# RFID_Reader_v0_1.net
KiCad netlist of a schematic drawn in EAGLE
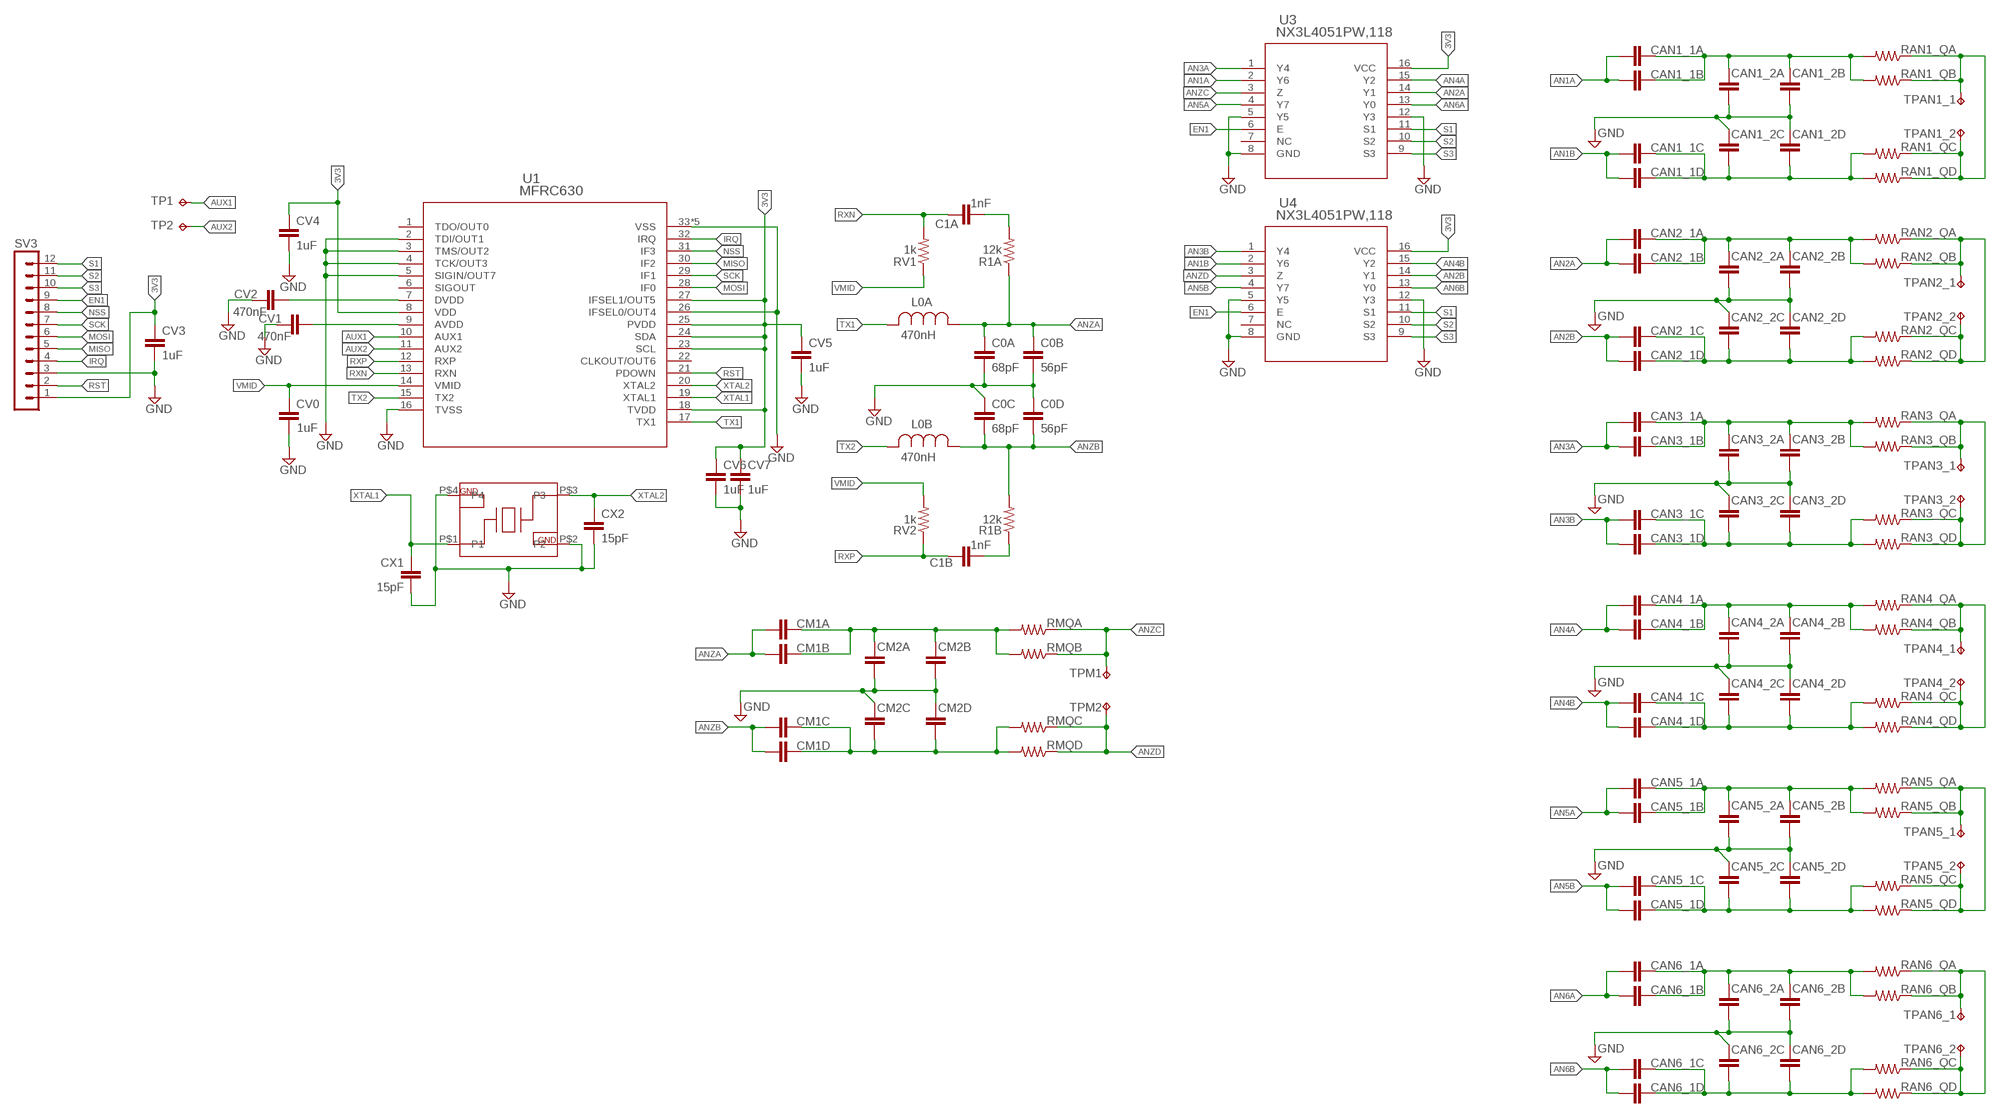
[diagram p0: schematic, sheet 1]

(export (version "E")
  (design (tool "Eeschema 10.0.6"))
  (components
    (comp (ref "C0A")
      (value "68pF")
      (footprint "eagle-import:C0805")
      (libsource (lib "eagle-import") (part "C-EUC0805"))
    )
    (comp (ref "C0B")
      (value "56pF")
      (footprint "eagle-import:C0805")
      (libsource (lib "eagle-import") (part "C-EUC0805"))
    )
    (comp (ref "C0C")
      (value "68pF")
      (footprint "eagle-import:C0805")
      (libsource (lib "eagle-import") (part "C-EUC0805"))
    )
    (comp (ref "C0D")
      (value "56pF")
      (footprint "eagle-import:C0805")
      (libsource (lib "eagle-import") (part "C-EUC0805"))
    )
    (comp (ref "C1A")
      (value "1nF")
      (footprint "eagle-import:C0805")
      (libsource (lib "eagle-import") (part "C-EUC0805"))
    )
    (comp (ref "C1B")
      (value "1nF")
      (footprint "eagle-import:C0805")
      (libsource (lib "eagle-import") (part "C-EUC0805"))
    )
    (comp (ref "CAN1_1A")
      (value "C-EUC0805")
      (footprint "eagle-import:C0805")
      (libsource (lib "eagle-import") (part "C-EUC0805"))
    )
    (comp (ref "CAN1_1B")
      (value "C-EUC0805")
      (footprint "eagle-import:C0805")
      (libsource (lib "eagle-import") (part "C-EUC0805"))
    )
    (comp (ref "CAN1_1C")
      (value "C-EUC0805")
      (footprint "eagle-import:C0805")
      (libsource (lib "eagle-import") (part "C-EUC0805"))
    )
    (comp (ref "CAN1_1D")
      (value "C-EUC0805")
      (footprint "eagle-import:C0805")
      (libsource (lib "eagle-import") (part "C-EUC0805"))
    )
    (comp (ref "CAN1_2A")
      (value "C-EUC0805")
      (footprint "eagle-import:C0805")
      (libsource (lib "eagle-import") (part "C-EUC0805"))
    )
    (comp (ref "CAN1_2B")
      (value "C-EUC0805")
      (footprint "eagle-import:C0805")
      (libsource (lib "eagle-import") (part "C-EUC0805"))
    )
    (comp (ref "CAN1_2C")
      (value "C-EUC0805")
      (footprint "eagle-import:C0805")
      (libsource (lib "eagle-import") (part "C-EUC0805"))
    )
    (comp (ref "CAN1_2D")
      (value "C-EUC0805")
      (footprint "eagle-import:C0805")
      (libsource (lib "eagle-import") (part "C-EUC0805"))
    )
    (comp (ref "CAN2_1A")
      (value "C-EUC0805")
      (footprint "eagle-import:C0805")
      (libsource (lib "eagle-import") (part "C-EUC0805"))
    )
    (comp (ref "CAN2_1B")
      (value "C-EUC0805")
      (footprint "eagle-import:C0805")
      (libsource (lib "eagle-import") (part "C-EUC0805"))
    )
    (comp (ref "CAN2_1C")
      (value "C-EUC0805")
      (footprint "eagle-import:C0805")
      (libsource (lib "eagle-import") (part "C-EUC0805"))
    )
    (comp (ref "CAN2_1D")
      (value "C-EUC0805")
      (footprint "eagle-import:C0805")
      (libsource (lib "eagle-import") (part "C-EUC0805"))
    )
    (comp (ref "CAN2_2A")
      (value "C-EUC0805")
      (footprint "eagle-import:C0805")
      (libsource (lib "eagle-import") (part "C-EUC0805"))
    )
    (comp (ref "CAN2_2B")
      (value "C-EUC0805")
      (footprint "eagle-import:C0805")
      (libsource (lib "eagle-import") (part "C-EUC0805"))
    )
    (comp (ref "CAN2_2C")
      (value "C-EUC0805")
      (footprint "eagle-import:C0805")
      (libsource (lib "eagle-import") (part "C-EUC0805"))
    )
    (comp (ref "CAN2_2D")
      (value "C-EUC0805")
      (footprint "eagle-import:C0805")
      (libsource (lib "eagle-import") (part "C-EUC0805"))
    )
    (comp (ref "CAN3_1A")
      (value "C-EUC0805")
      (footprint "eagle-import:C0805")
      (libsource (lib "eagle-import") (part "C-EUC0805"))
    )
    (comp (ref "CAN3_1B")
      (value "C-EUC0805")
      (footprint "eagle-import:C0805")
      (libsource (lib "eagle-import") (part "C-EUC0805"))
    )
    (comp (ref "CAN3_1C")
      (value "C-EUC0805")
      (footprint "eagle-import:C0805")
      (libsource (lib "eagle-import") (part "C-EUC0805"))
    )
    (comp (ref "CAN3_1D")
      (value "C-EUC0805")
      (footprint "eagle-import:C0805")
      (libsource (lib "eagle-import") (part "C-EUC0805"))
    )
    (comp (ref "CAN3_2A")
      (value "C-EUC0805")
      (footprint "eagle-import:C0805")
      (libsource (lib "eagle-import") (part "C-EUC0805"))
    )
    (comp (ref "CAN3_2B")
      (value "C-EUC0805")
      (footprint "eagle-import:C0805")
      (libsource (lib "eagle-import") (part "C-EUC0805"))
    )
    (comp (ref "CAN3_2C")
      (value "C-EUC0805")
      (footprint "eagle-import:C0805")
      (libsource (lib "eagle-import") (part "C-EUC0805"))
    )
    (comp (ref "CAN3_2D")
      (value "C-EUC0805")
      (footprint "eagle-import:C0805")
      (libsource (lib "eagle-import") (part "C-EUC0805"))
    )
    (comp (ref "CAN4_1A")
      (value "C-EUC0805")
      (footprint "eagle-import:C0805")
      (libsource (lib "eagle-import") (part "C-EUC0805"))
    )
    (comp (ref "CAN4_1B")
      (value "C-EUC0805")
      (footprint "eagle-import:C0805")
      (libsource (lib "eagle-import") (part "C-EUC0805"))
    )
    (comp (ref "CAN4_1C")
      (value "C-EUC0805")
      (footprint "eagle-import:C0805")
      (libsource (lib "eagle-import") (part "C-EUC0805"))
    )
    (comp (ref "CAN4_1D")
      (value "C-EUC0805")
      (footprint "eagle-import:C0805")
      (libsource (lib "eagle-import") (part "C-EUC0805"))
    )
    (comp (ref "CAN4_2A")
      (value "C-EUC0805")
      (footprint "eagle-import:C0805")
      (libsource (lib "eagle-import") (part "C-EUC0805"))
    )
    (comp (ref "CAN4_2B")
      (value "C-EUC0805")
      (footprint "eagle-import:C0805")
      (libsource (lib "eagle-import") (part "C-EUC0805"))
    )
    (comp (ref "CAN4_2C")
      (value "C-EUC0805")
      (footprint "eagle-import:C0805")
      (libsource (lib "eagle-import") (part "C-EUC0805"))
    )
    (comp (ref "CAN4_2D")
      (value "C-EUC0805")
      (footprint "eagle-import:C0805")
      (libsource (lib "eagle-import") (part "C-EUC0805"))
    )
    (comp (ref "CAN5_1A")
      (value "C-EUC0805")
      (footprint "eagle-import:C0805")
      (libsource (lib "eagle-import") (part "C-EUC0805"))
    )
    (comp (ref "CAN5_1B")
      (value "C-EUC0805")
      (footprint "eagle-import:C0805")
      (libsource (lib "eagle-import") (part "C-EUC0805"))
    )
    (comp (ref "CAN5_1C")
      (value "C-EUC0805")
      (footprint "eagle-import:C0805")
      (libsource (lib "eagle-import") (part "C-EUC0805"))
    )
    (comp (ref "CAN5_1D")
      (value "C-EUC0805")
      (footprint "eagle-import:C0805")
      (libsource (lib "eagle-import") (part "C-EUC0805"))
    )
    (comp (ref "CAN5_2A")
      (value "C-EUC0805")
      (footprint "eagle-import:C0805")
      (libsource (lib "eagle-import") (part "C-EUC0805"))
    )
    (comp (ref "CAN5_2B")
      (value "C-EUC0805")
      (footprint "eagle-import:C0805")
      (libsource (lib "eagle-import") (part "C-EUC0805"))
    )
    (comp (ref "CAN5_2C")
      (value "C-EUC0805")
      (footprint "eagle-import:C0805")
      (libsource (lib "eagle-import") (part "C-EUC0805"))
    )
    (comp (ref "CAN5_2D")
      (value "C-EUC0805")
      (footprint "eagle-import:C0805")
      (libsource (lib "eagle-import") (part "C-EUC0805"))
    )
    (comp (ref "CAN6_1A")
      (value "C-EUC0805")
      (footprint "eagle-import:C0805")
      (libsource (lib "eagle-import") (part "C-EUC0805"))
    )
    (comp (ref "CAN6_1B")
      (value "C-EUC0805")
      (footprint "eagle-import:C0805")
      (libsource (lib "eagle-import") (part "C-EUC0805"))
    )
    (comp (ref "CAN6_1C")
      (value "C-EUC0805")
      (footprint "eagle-import:C0805")
      (libsource (lib "eagle-import") (part "C-EUC0805"))
    )
    (comp (ref "CAN6_1D")
      (value "C-EUC0805")
      (footprint "eagle-import:C0805")
      (libsource (lib "eagle-import") (part "C-EUC0805"))
    )
    (comp (ref "CAN6_2A")
      (value "C-EUC0805")
      (footprint "eagle-import:C0805")
      (libsource (lib "eagle-import") (part "C-EUC0805"))
    )
    (comp (ref "CAN6_2B")
      (value "C-EUC0805")
      (footprint "eagle-import:C0805")
      (libsource (lib "eagle-import") (part "C-EUC0805"))
    )
    (comp (ref "CAN6_2C")
      (value "C-EUC0805")
      (footprint "eagle-import:C0805")
      (libsource (lib "eagle-import") (part "C-EUC0805"))
    )
    (comp (ref "CAN6_2D")
      (value "C-EUC0805")
      (footprint "eagle-import:C0805")
      (libsource (lib "eagle-import") (part "C-EUC0805"))
    )
    (comp (ref "CM1A")
      (value "C-EUC0805")
      (footprint "eagle-import:C0805")
      (libsource (lib "eagle-import") (part "C-EUC0805"))
    )
    (comp (ref "CM1B")
      (value "C-EUC0805")
      (footprint "eagle-import:C0805")
      (libsource (lib "eagle-import") (part "C-EUC0805"))
    )
    (comp (ref "CM1C")
      (value "C-EUC0805")
      (footprint "eagle-import:C0805")
      (libsource (lib "eagle-import") (part "C-EUC0805"))
    )
    (comp (ref "CM1D")
      (value "C-EUC0805")
      (footprint "eagle-import:C0805")
      (libsource (lib "eagle-import") (part "C-EUC0805"))
    )
    (comp (ref "CM2A")
      (value "C-EUC0805")
      (footprint "eagle-import:C0805")
      (libsource (lib "eagle-import") (part "C-EUC0805"))
    )
    (comp (ref "CM2B")
      (value "C-EUC0805")
      (footprint "eagle-import:C0805")
      (libsource (lib "eagle-import") (part "C-EUC0805"))
    )
    (comp (ref "CM2C")
      (value "C-EUC0805")
      (footprint "eagle-import:C0805")
      (libsource (lib "eagle-import") (part "C-EUC0805"))
    )
    (comp (ref "CM2D")
      (value "C-EUC0805")
      (footprint "eagle-import:C0805")
      (libsource (lib "eagle-import") (part "C-EUC0805"))
    )
    (comp (ref "CV0")
      (value "1uF")
      (footprint "eagle-import:C0402")
      (libsource (lib "eagle-import") (part "C-EUC0402"))
    )
    (comp (ref "CV1")
      (value "470nF")
      (footprint "eagle-import:C0402")
      (libsource (lib "eagle-import") (part "C-EUC0402"))
    )
    (comp (ref "CV2")
      (value "470nF")
      (footprint "eagle-import:C0402")
      (libsource (lib "eagle-import") (part "C-EUC0402"))
    )
    (comp (ref "CV3")
      (value "1uF")
      (footprint "eagle-import:C0402")
      (libsource (lib "eagle-import") (part "C-EUC0402"))
    )
    (comp (ref "CV4")
      (value "1uF")
      (footprint "eagle-import:C0402")
      (libsource (lib "eagle-import") (part "C-EUC0402"))
    )
    (comp (ref "CV5")
      (value "1uF")
      (footprint "eagle-import:C0402")
      (libsource (lib "eagle-import") (part "C-EUC0402"))
    )
    (comp (ref "CV6")
      (value "1uF")
      (footprint "eagle-import:C0402")
      (libsource (lib "eagle-import") (part "C-EUC0402"))
    )
    (comp (ref "CV7")
      (value "1uF")
      (footprint "eagle-import:C0402")
      (libsource (lib "eagle-import") (part "C-EUC0402"))
    )
    (comp (ref "CX1")
      (value "15pF")
      (footprint "eagle-import:C0402")
      (libsource (lib "eagle-import") (part "C-EUC0402"))
    )
    (comp (ref "CX2")
      (value "15pF")
      (footprint "eagle-import:C0402")
      (libsource (lib "eagle-import") (part "C-EUC0402"))
    )
    (comp (ref "L0A")
      (value "470nH")
      (footprint "eagle-import:IND_BOURNS_CE201210_C")
      (fields
        (field (name "MANUFACTURER_PART_NUMBER") "CE201210-R47J")
        (field (name "COPYRIGHT") "Copyright (C) 2024 Ultra Librarian. All rights reserved.")
      )
      (libsource (lib "eagle-import") (part "CE201210-R47JIND_BOURNS_CE201210_C"))
    )
    (comp (ref "L0B")
      (value "470nH")
      (footprint "eagle-import:IND_BOURNS_CE201210_C")
      (fields
        (field (name "MANUFACTURER_PART_NUMBER") "CE201210-R47J")
        (field (name "COPYRIGHT") "Copyright (C) 2024 Ultra Librarian. All rights reserved.")
      )
      (libsource (lib "eagle-import") (part "CE201210-R47JIND_BOURNS_CE201210_C"))
    )
    (comp (ref "R1A")
      (value "12k")
      (footprint "eagle-import:R0805")
      (libsource (lib "eagle-import") (part "R-US_R0805"))
    )
    (comp (ref "R1B")
      (value "12k")
      (footprint "eagle-import:R0805")
      (libsource (lib "eagle-import") (part "R-US_R0805"))
    )
    (comp (ref "RAN1_QA")
      (value "R-US_R0805")
      (footprint "eagle-import:R0805")
      (libsource (lib "eagle-import") (part "R-US_R0805"))
    )
    (comp (ref "RAN1_QB")
      (value "R-US_R0805")
      (footprint "eagle-import:R0805")
      (libsource (lib "eagle-import") (part "R-US_R0805"))
    )
    (comp (ref "RAN1_QC")
      (value "R-US_R0805")
      (footprint "eagle-import:R0805")
      (libsource (lib "eagle-import") (part "R-US_R0805"))
    )
    (comp (ref "RAN1_QD")
      (value "R-US_R0805")
      (footprint "eagle-import:R0805")
      (libsource (lib "eagle-import") (part "R-US_R0805"))
    )
    (comp (ref "RAN2_QA")
      (value "R-US_R0805")
      (footprint "eagle-import:R0805")
      (libsource (lib "eagle-import") (part "R-US_R0805"))
    )
    (comp (ref "RAN2_QB")
      (value "R-US_R0805")
      (footprint "eagle-import:R0805")
      (libsource (lib "eagle-import") (part "R-US_R0805"))
    )
    (comp (ref "RAN2_QC")
      (value "R-US_R0805")
      (footprint "eagle-import:R0805")
      (libsource (lib "eagle-import") (part "R-US_R0805"))
    )
    (comp (ref "RAN2_QD")
      (value "R-US_R0805")
      (footprint "eagle-import:R0805")
      (libsource (lib "eagle-import") (part "R-US_R0805"))
    )
    (comp (ref "RAN3_QA")
      (value "R-US_R0805")
      (footprint "eagle-import:R0805")
      (libsource (lib "eagle-import") (part "R-US_R0805"))
    )
    (comp (ref "RAN3_QB")
      (value "R-US_R0805")
      (footprint "eagle-import:R0805")
      (libsource (lib "eagle-import") (part "R-US_R0805"))
    )
    (comp (ref "RAN3_QC")
      (value "R-US_R0805")
      (footprint "eagle-import:R0805")
      (libsource (lib "eagle-import") (part "R-US_R0805"))
    )
    (comp (ref "RAN3_QD")
      (value "R-US_R0805")
      (footprint "eagle-import:R0805")
      (libsource (lib "eagle-import") (part "R-US_R0805"))
    )
    (comp (ref "RAN4_QA")
      (value "R-US_R0805")
      (footprint "eagle-import:R0805")
      (libsource (lib "eagle-import") (part "R-US_R0805"))
    )
    (comp (ref "RAN4_QB")
      (value "R-US_R0805")
      (footprint "eagle-import:R0805")
      (libsource (lib "eagle-import") (part "R-US_R0805"))
    )
    (comp (ref "RAN4_QC")
      (value "R-US_R0805")
      (footprint "eagle-import:R0805")
      (libsource (lib "eagle-import") (part "R-US_R0805"))
    )
    (comp (ref "RAN4_QD")
      (value "R-US_R0805")
      (footprint "eagle-import:R0805")
      (libsource (lib "eagle-import") (part "R-US_R0805"))
    )
    (comp (ref "RAN5_QA")
      (value "R-US_R0805")
      (footprint "eagle-import:R0805")
      (libsource (lib "eagle-import") (part "R-US_R0805"))
    )
    (comp (ref "RAN5_QB")
      (value "R-US_R0805")
      (footprint "eagle-import:R0805")
      (libsource (lib "eagle-import") (part "R-US_R0805"))
    )
    (comp (ref "RAN5_QC")
      (value "R-US_R0805")
      (footprint "eagle-import:R0805")
      (libsource (lib "eagle-import") (part "R-US_R0805"))
    )
    (comp (ref "RAN5_QD")
      (value "R-US_R0805")
      (footprint "eagle-import:R0805")
      (libsource (lib "eagle-import") (part "R-US_R0805"))
    )
    (comp (ref "RAN6_QA")
      (value "R-US_R0805")
      (footprint "eagle-import:R0805")
      (libsource (lib "eagle-import") (part "R-US_R0805"))
    )
    (comp (ref "RAN6_QB")
      (value "R-US_R0805")
      (footprint "eagle-import:R0805")
      (libsource (lib "eagle-import") (part "R-US_R0805"))
    )
    (comp (ref "RAN6_QC")
      (value "R-US_R0805")
      (footprint "eagle-import:R0805")
      (libsource (lib "eagle-import") (part "R-US_R0805"))
    )
    (comp (ref "RAN6_QD")
      (value "R-US_R0805")
      (footprint "eagle-import:R0805")
      (libsource (lib "eagle-import") (part "R-US_R0805"))
    )
    (comp (ref "RMQA")
      (value "R-US_R0805")
      (footprint "eagle-import:R0805")
      (libsource (lib "eagle-import") (part "R-US_R0805"))
    )
    (comp (ref "RMQB")
      (value "R-US_R0805")
      (footprint "eagle-import:R0805")
      (libsource (lib "eagle-import") (part "R-US_R0805"))
    )
    (comp (ref "RMQC")
      (value "R-US_R0805")
      (footprint "eagle-import:R0805")
      (libsource (lib "eagle-import") (part "R-US_R0805"))
    )
    (comp (ref "RMQD")
      (value "R-US_R0805")
      (footprint "eagle-import:R0805")
      (libsource (lib "eagle-import") (part "R-US_R0805"))
    )
    (comp (ref "RV1")
      (value "1k")
      (footprint "eagle-import:R0805")
      (libsource (lib "eagle-import") (part "R-US_R0805"))
    )
    (comp (ref "RV2")
      (value "1k")
      (footprint "eagle-import:R0805")
      (libsource (lib "eagle-import") (part "R-US_R0805"))
    )
    (comp (ref "SV3")
      (value "MA12-1")
      (footprint "eagle-import:MA12-1")
      (libsource (lib "eagle-import") (part "MA12-1"))
    )
    (comp (ref "TP1")
      (value "TPTP10R")
      (footprint "eagle-import:TP10R")
      (libsource (lib "eagle-import") (part "TPTP10R"))
    )
    (comp (ref "TP2")
      (value "TPTP10R")
      (footprint "eagle-import:TP10R")
      (libsource (lib "eagle-import") (part "TPTP10R"))
    )
    (comp (ref "TPAN1_1")
      (value "TPTP10R")
      (footprint "eagle-import:TP10R")
      (libsource (lib "eagle-import") (part "TPTP10R"))
    )
    (comp (ref "TPAN1_2")
      (value "TPTP10R")
      (footprint "eagle-import:TP10R")
      (libsource (lib "eagle-import") (part "TPTP10R"))
    )
    (comp (ref "TPAN2_1")
      (value "TPTP10R")
      (footprint "eagle-import:TP10R")
      (libsource (lib "eagle-import") (part "TPTP10R"))
    )
    (comp (ref "TPAN2_2")
      (value "TPTP10R")
      (footprint "eagle-import:TP10R")
      (libsource (lib "eagle-import") (part "TPTP10R"))
    )
    (comp (ref "TPAN3_1")
      (value "TPTP10R")
      (footprint "eagle-import:TP10R")
      (libsource (lib "eagle-import") (part "TPTP10R"))
    )
    (comp (ref "TPAN3_2")
      (value "TPTP10R")
      (footprint "eagle-import:TP10R")
      (libsource (lib "eagle-import") (part "TPTP10R"))
    )
    (comp (ref "TPAN4_1")
      (value "TPTP10R")
      (footprint "eagle-import:TP10R")
      (libsource (lib "eagle-import") (part "TPTP10R"))
    )
    (comp (ref "TPAN4_2")
      (value "TPTP10R")
      (footprint "eagle-import:TP10R")
      (libsource (lib "eagle-import") (part "TPTP10R"))
    )
    (comp (ref "TPAN5_1")
      (value "TPTP10R")
      (footprint "eagle-import:TP10R")
      (libsource (lib "eagle-import") (part "TPTP10R"))
    )
    (comp (ref "TPAN5_2")
      (value "TPTP10R")
      (footprint "eagle-import:TP10R")
      (libsource (lib "eagle-import") (part "TPTP10R"))
    )
    (comp (ref "TPAN6_1")
      (value "TPTP10R")
      (footprint "eagle-import:TP10R")
      (libsource (lib "eagle-import") (part "TPTP10R"))
    )
    (comp (ref "TPAN6_2")
      (value "TPTP10R")
      (footprint "eagle-import:TP10R")
      (libsource (lib "eagle-import") (part "TPTP10R"))
    )
    (comp (ref "TPM1")
      (value "TPTP10R")
      (footprint "eagle-import:TP10R")
      (libsource (lib "eagle-import") (part "TPTP10R"))
    )
    (comp (ref "TPM2")
      (value "TPTP10R")
      (footprint "eagle-import:TP10R")
      (libsource (lib "eagle-import") (part "TPTP10R"))
    )
    (comp (ref "U1")
      (value "MFRC630")
      (footprint "eagle-import:HVQFN32_SOT617-1_NXP-M")
      (fields
        (field (name "MANUFACTURER_PART_NUMBER") "MFRC63002HN,118")
        (field (name "COPYRIGHT") "Copyright (C) 2024 Ultra Librarian. All rights reserved.")
      )
      (libsource (lib "eagle-import") (part "MFRC63002HN,118HVQFN32_SOT617-1_NXP-M"))
    )
    (comp (ref "U2")
      (value "E3SB27")
      (footprint "eagle-import:DFN320X250X75-4N")
      (libsource (lib "eagle-import") (part "E3SB27E0X000VEE3SB27E0X000VE"))
    )
    (comp (ref "U3")
      (value "NX3L4051PW,118")
      (footprint "eagle-import:TSSOP16_NXP-M")
      (fields (field (name "COPYRIGHT") "Copyright (C) 2024 Ultra Librarian. All rights reserved."))
      (libsource (lib "eagle-import") (part "NX3L4051PW,118TSSOP16_NXP-M"))
    )
    (comp (ref "U4")
      (value "NX3L4051PW,118")
      (footprint "eagle-import:TSSOP16_NXP-M")
      (fields (field (name "COPYRIGHT") "Copyright (C) 2024 Ultra Librarian. All rights reserved."))
      (libsource (lib "eagle-import") (part "NX3L4051PW,118TSSOP16_NXP-M"))
    )
  )
  (nets
    (net (code "1") (name "3V3") (class "Default")
      (node (ref "CV3") (pin "1") (pinfunction "1_1") (pintype "passive"))
      (node (ref "CV4") (pin "1") (pinfunction "1_1") (pintype "passive"))
      (node (ref "CV5") (pin "1") (pinfunction "1_1") (pintype "passive"))
      (node (ref "CV6") (pin "1") (pinfunction "1_1") (pintype "passive"))
      (node (ref "CV7") (pin "1") (pinfunction "1_1") (pintype "passive"))
      (node (ref "SV3") (pin "1") (pinfunction "1_1") (pintype "passive"))
      (node (ref "U1") (pin "18") (pinfunction "TVDD_18") (pintype "power_in"))
      (node (ref "U1") (pin "23") (pinfunction "SCL_23") (pintype "output"))
      (node (ref "U1") (pin "24") (pinfunction "SDA_24") (pintype "bidirectional"))
      (node (ref "U1") (pin "25") (pinfunction "PVDD_25") (pintype "power_in"))
      (node (ref "U1") (pin "27") (pinfunction "IFSEL1/OUT5_27") (pintype "input"))
      (node (ref "U1") (pin "8") (pinfunction "VDD_8") (pintype "power_in"))
      (node (ref "U3") (pin "16") (pinfunction "VCC_16") (pintype "power_in"))
      (node (ref "U4") (pin "16") (pinfunction "VCC_16") (pintype "power_in"))
    )
    (net (code "2") (name "AN1A") (class "Default")
      (node (ref "CAN1_1A") (pin "2") (pinfunction "2_2") (pintype "passive"))
      (node (ref "CAN1_1B") (pin "2") (pinfunction "2_2") (pintype "passive"))
      (node (ref "U3") (pin "2") (pinfunction "Y6_2") (pintype "bidirectional"))
    )
    (net (code "3") (name "AN1B") (class "Default")
      (node (ref "CAN1_1C") (pin "2") (pinfunction "2_2") (pintype "passive"))
      (node (ref "CAN1_1D") (pin "2") (pinfunction "2_2") (pintype "passive"))
      (node (ref "U4") (pin "2") (pinfunction "Y6_2") (pintype "bidirectional"))
    )
    (net (code "4") (name "AN2A") (class "Default")
      (node (ref "CAN2_1A") (pin "2") (pinfunction "2_2") (pintype "passive"))
      (node (ref "CAN2_1B") (pin "2") (pinfunction "2_2") (pintype "passive"))
      (node (ref "U3") (pin "14") (pinfunction "Y1_14") (pintype "bidirectional"))
    )
    (net (code "5") (name "AN2B") (class "Default")
      (node (ref "CAN2_1C") (pin "2") (pinfunction "2_2") (pintype "passive"))
      (node (ref "CAN2_1D") (pin "2") (pinfunction "2_2") (pintype "passive"))
      (node (ref "U4") (pin "14") (pinfunction "Y1_14") (pintype "bidirectional"))
    )
    (net (code "6") (name "AN3A") (class "Default")
      (node (ref "CAN3_1A") (pin "2") (pinfunction "2_2") (pintype "passive"))
      (node (ref "CAN3_1B") (pin "2") (pinfunction "2_2") (pintype "passive"))
      (node (ref "U3") (pin "1") (pinfunction "Y4_1") (pintype "bidirectional"))
    )
    (net (code "7") (name "AN3B") (class "Default")
      (node (ref "CAN3_1C") (pin "2") (pinfunction "2_2") (pintype "passive"))
      (node (ref "CAN3_1D") (pin "2") (pinfunction "2_2") (pintype "passive"))
      (node (ref "U4") (pin "1") (pinfunction "Y4_1") (pintype "bidirectional"))
    )
    (net (code "8") (name "AN4A") (class "Default")
      (node (ref "CAN4_1A") (pin "2") (pinfunction "2_2") (pintype "passive"))
      (node (ref "CAN4_1B") (pin "2") (pinfunction "2_2") (pintype "passive"))
      (node (ref "U3") (pin "15") (pinfunction "Y2_15") (pintype "bidirectional"))
    )
    (net (code "9") (name "AN4B") (class "Default")
      (node (ref "CAN4_1C") (pin "2") (pinfunction "2_2") (pintype "passive"))
      (node (ref "CAN4_1D") (pin "2") (pinfunction "2_2") (pintype "passive"))
      (node (ref "U4") (pin "15") (pinfunction "Y2_15") (pintype "bidirectional"))
    )
    (net (code "10") (name "AN5A") (class "Default")
      (node (ref "CAN5_1A") (pin "2") (pinfunction "2_2") (pintype "passive"))
      (node (ref "CAN5_1B") (pin "2") (pinfunction "2_2") (pintype "passive"))
      (node (ref "U3") (pin "4") (pinfunction "Y7_4") (pintype "bidirectional"))
    )
    (net (code "11") (name "AN5B") (class "Default")
      (node (ref "CAN5_1C") (pin "2") (pinfunction "2_2") (pintype "passive"))
      (node (ref "CAN5_1D") (pin "2") (pinfunction "2_2") (pintype "passive"))
      (node (ref "U4") (pin "4") (pinfunction "Y7_4") (pintype "bidirectional"))
    )
    (net (code "12") (name "AN6A") (class "Default")
      (node (ref "CAN6_1A") (pin "2") (pinfunction "2_2") (pintype "passive"))
      (node (ref "CAN6_1B") (pin "2") (pinfunction "2_2") (pintype "passive"))
      (node (ref "U3") (pin "13") (pinfunction "Y0_13") (pintype "bidirectional"))
    )
    (net (code "13") (name "AN6B") (class "Default")
      (node (ref "CAN6_1C") (pin "2") (pinfunction "2_2") (pintype "passive"))
      (node (ref "CAN6_1D") (pin "2") (pinfunction "2_2") (pintype "passive"))
      (node (ref "U4") (pin "13") (pinfunction "Y0_13") (pintype "bidirectional"))
    )
    (net (code "14") (name "ANZA") (class "Default")
      (node (ref "C0A") (pin "1") (pinfunction "1_1") (pintype "passive"))
      (node (ref "C0B") (pin "1") (pinfunction "1_1") (pintype "passive"))
      (node (ref "CM1A") (pin "2") (pinfunction "2_2") (pintype "passive"))
      (node (ref "CM1B") (pin "2") (pinfunction "2_2") (pintype "passive"))
      (node (ref "L0A") (pin "1") (pinfunction "1_1") (pintype "passive"))
      (node (ref "R1A") (pin "1") (pinfunction "1_1") (pintype "passive"))
    )
    (net (code "15") (name "ANZB") (class "Default")
      (node (ref "C0C") (pin "2") (pinfunction "2_2") (pintype "passive"))
      (node (ref "C0D") (pin "2") (pinfunction "2_2") (pintype "passive"))
      (node (ref "CM1C") (pin "2") (pinfunction "2_2") (pintype "passive"))
      (node (ref "CM1D") (pin "2") (pinfunction "2_2") (pintype "passive"))
      (node (ref "L0B") (pin "1") (pinfunction "1_1") (pintype "passive"))
      (node (ref "R1B") (pin "2") (pinfunction "2_2") (pintype "passive"))
    )
    (net (code "16") (name "ANZC") (class "Default")
      (node (ref "RMQA") (pin "1") (pinfunction "1_1") (pintype "passive"))
      (node (ref "RMQB") (pin "1") (pinfunction "1_1") (pintype "passive"))
      (node (ref "TPM1") (pin "TP") (pinfunction "TP_TP") (pintype "input"))
      (node (ref "U3") (pin "3") (pinfunction "Z_3") (pintype "bidirectional"))
    )
    (net (code "17") (name "ANZD") (class "Default")
      (node (ref "RMQC") (pin "1") (pinfunction "1_1") (pintype "passive"))
      (node (ref "RMQD") (pin "1") (pinfunction "1_1") (pintype "passive"))
      (node (ref "TPM2") (pin "TP") (pinfunction "TP_TP") (pintype "input"))
      (node (ref "U4") (pin "3") (pinfunction "Z_3") (pintype "bidirectional"))
    )
    (net (code "18") (name "AUX1") (class "Default")
      (node (ref "TP1") (pin "TP") (pinfunction "TP_TP") (pintype "input"))
      (node (ref "U1") (pin "10") (pinfunction "AUX1_10") (pintype "output"))
    )
    (net (code "19") (name "AUX2") (class "Default")
      (node (ref "TP2") (pin "TP") (pinfunction "TP_TP") (pintype "input"))
      (node (ref "U1") (pin "11") (pinfunction "AUX2_11") (pintype "output"))
    )
    (net (code "20") (name "EN1") (class "Default")
      (node (ref "SV3") (pin "9") (pinfunction "9_9") (pintype "passive"))
      (node (ref "U3") (pin "6") (pinfunction "E_6") (pintype "input"))
      (node (ref "U4") (pin "6") (pinfunction "E_6") (pintype "input"))
    )
    (net (code "21") (name "GND") (class "Default")
      (node (ref "C0A") (pin "2") (pinfunction "2_2") (pintype "passive"))
      (node (ref "C0B") (pin "2") (pinfunction "2_2") (pintype "passive"))
      (node (ref "C0C") (pin "1") (pinfunction "1_1") (pintype "passive"))
      (node (ref "C0D") (pin "1") (pinfunction "1_1") (pintype "passive"))
      (node (ref "CAN1_2A") (pin "2") (pinfunction "2_2") (pintype "passive"))
      (node (ref "CAN1_2B") (pin "2") (pinfunction "2_2") (pintype "passive"))
      (node (ref "CAN1_2C") (pin "1") (pinfunction "1_1") (pintype "passive"))
      (node (ref "CAN1_2D") (pin "1") (pinfunction "1_1") (pintype "passive"))
      (node (ref "CAN2_2A") (pin "2") (pinfunction "2_2") (pintype "passive"))
      (node (ref "CAN2_2B") (pin "2") (pinfunction "2_2") (pintype "passive"))
      (node (ref "CAN2_2C") (pin "1") (pinfunction "1_1") (pintype "passive"))
      (node (ref "CAN2_2D") (pin "1") (pinfunction "1_1") (pintype "passive"))
      (node (ref "CAN3_2A") (pin "2") (pinfunction "2_2") (pintype "passive"))
      (node (ref "CAN3_2B") (pin "2") (pinfunction "2_2") (pintype "passive"))
      (node (ref "CAN3_2C") (pin "1") (pinfunction "1_1") (pintype "passive"))
      (node (ref "CAN3_2D") (pin "1") (pinfunction "1_1") (pintype "passive"))
      (node (ref "CAN4_2A") (pin "2") (pinfunction "2_2") (pintype "passive"))
      (node (ref "CAN4_2B") (pin "2") (pinfunction "2_2") (pintype "passive"))
      (node (ref "CAN4_2C") (pin "1") (pinfunction "1_1") (pintype "passive"))
      (node (ref "CAN4_2D") (pin "1") (pinfunction "1_1") (pintype "passive"))
      (node (ref "CAN5_2A") (pin "2") (pinfunction "2_2") (pintype "passive"))
      (node (ref "CAN5_2B") (pin "2") (pinfunction "2_2") (pintype "passive"))
      (node (ref "CAN5_2C") (pin "1") (pinfunction "1_1") (pintype "passive"))
      (node (ref "CAN5_2D") (pin "1") (pinfunction "1_1") (pintype "passive"))
      (node (ref "CAN6_2A") (pin "2") (pinfunction "2_2") (pintype "passive"))
      (node (ref "CAN6_2B") (pin "2") (pinfunction "2_2") (pintype "passive"))
      (node (ref "CAN6_2C") (pin "1") (pinfunction "1_1") (pintype "passive"))
      (node (ref "CAN6_2D") (pin "1") (pinfunction "1_1") (pintype "passive"))
      (node (ref "CM2A") (pin "2") (pinfunction "2_2") (pintype "passive"))
      (node (ref "CM2B") (pin "2") (pinfunction "2_2") (pintype "passive"))
      (node (ref "CM2C") (pin "1") (pinfunction "1_1") (pintype "passive"))
      (node (ref "CM2D") (pin "1") (pinfunction "1_1") (pintype "passive"))
      (node (ref "CV0") (pin "2") (pinfunction "2_2") (pintype "passive"))
      (node (ref "CV1") (pin "2") (pinfunction "2_2") (pintype "passive"))
      (node (ref "CV2") (pin "2") (pinfunction "2_2") (pintype "passive"))
      (node (ref "CV3") (pin "2") (pinfunction "2_2") (pintype "passive"))
      (node (ref "CV4") (pin "2") (pinfunction "2_2") (pintype "passive"))
      (node (ref "CV5") (pin "2") (pinfunction "2_2") (pintype "passive"))
      (node (ref "CV6") (pin "2") (pinfunction "2_2") (pintype "passive"))
      (node (ref "CV7") (pin "2") (pinfunction "2_2") (pintype "passive"))
      (node (ref "CX1") (pin "2") (pinfunction "2_2") (pintype "passive"))
      (node (ref "CX2") (pin "2") (pinfunction "2_2") (pintype "passive"))
      (node (ref "SV3") (pin "3") (pinfunction "3_3") (pintype "passive"))
      (node (ref "U1") (pin "16") (pinfunction "TVSS_16") (pintype "passive"))
      (node (ref "U1") (pin "2") (pinfunction "TDI/OUT1_2") (pintype "input"))
      (node (ref "U1") (pin "26") (pinfunction "IFSEL0/OUT4_26") (pintype "input"))
      (node (ref "U1") (pin "3") (pinfunction "TMS/OUT2_3") (pintype "input"))
      (node (ref "U1") (pin "33") (pinfunction "VSS_33") (pintype "passive"))
      (node (ref "U1") (pin "4") (pinfunction "TCK/OUT3_4") (pintype "input"))
      (node (ref "U1") (pin "5") (pinfunction "SIGIN/OUT7_5") (pintype "bidirectional"))
      (node (ref "U1") (pin "P$1") (pinfunction "VSS_P$1") (pintype "passive"))
      (node (ref "U1") (pin "P$2") (pinfunction "VSS_P$2") (pintype "passive"))
      (node (ref "U1") (pin "P$3") (pinfunction "VSS_P$3") (pintype "passive"))
      (node (ref "U1") (pin "P$4") (pinfunction "VSS_P$4") (pintype "passive"))
      (node (ref "U2") (pin "P$2") (pinfunction "P2_P$2") (pintype "input"))
      (node (ref "U2") (pin "P$4") (pinfunction "P4_P$4") (pintype "input"))
      (node (ref "U3") (pin "12") (pinfunction "Y3_12") (pintype "bidirectional"))
      (node (ref "U3") (pin "5") (pinfunction "Y5_5") (pintype "bidirectional"))
      (node (ref "U3") (pin "8") (pinfunction "GND_8") (pintype "passive"))
      (node (ref "U4") (pin "12") (pinfunction "Y3_12") (pintype "bidirectional"))
      (node (ref "U4") (pin "5") (pinfunction "Y5_5") (pintype "bidirectional"))
      (node (ref "U4") (pin "8") (pinfunction "GND_8") (pintype "passive"))
    )
    (net (code "22") (name "IRQ") (class "Default")
      (node (ref "SV3") (pin "4") (pinfunction "4_4") (pintype "passive"))
      (node (ref "U1") (pin "32") (pinfunction "IRQ_32") (pintype "output"))
    )
    (net (code "23") (name "MISO") (class "Default")
      (node (ref "SV3") (pin "5") (pinfunction "5_5") (pintype "passive"))
      (node (ref "U1") (pin "30") (pinfunction "IF2_30") (pintype "bidirectional"))
    )
    (net (code "24") (name "MOSI") (class "Default")
      (node (ref "SV3") (pin "6") (pinfunction "6_6") (pintype "passive"))
      (node (ref "U1") (pin "28") (pinfunction "IF0_28") (pintype "bidirectional"))
    )
    (net (code "25") (name "NSS") (class "Default")
      (node (ref "SV3") (pin "8") (pinfunction "8_8") (pintype "passive"))
      (node (ref "U1") (pin "31") (pinfunction "IF3_31") (pintype "bidirectional"))
    )
    (net (code "26") (name "Net-(C1A-Pad2)") (class "Default")
      (node (ref "C1A") (pin "2") (pinfunction "2_2") (pintype "passive"))
      (node (ref "R1A") (pin "2") (pinfunction "2_2") (pintype "passive"))
    )
    (net (code "27") (name "Net-(C1B-Pad2)") (class "Default")
      (node (ref "C1B") (pin "2") (pinfunction "2_2") (pintype "passive"))
      (node (ref "R1B") (pin "1") (pinfunction "1_1") (pintype "passive"))
    )
    (net (code "28") (name "Net-(CAN1_1A-Pad1)") (class "Default")
      (node (ref "CAN1_1A") (pin "1") (pinfunction "1_1") (pintype "passive"))
      (node (ref "CAN1_1B") (pin "1") (pinfunction "1_1") (pintype "passive"))
      (node (ref "CAN1_2A") (pin "1") (pinfunction "1_1") (pintype "passive"))
      (node (ref "CAN1_2B") (pin "1") (pinfunction "1_1") (pintype "passive"))
      (node (ref "RAN1_QA") (pin "2") (pinfunction "2_2") (pintype "passive"))
      (node (ref "RAN1_QB") (pin "2") (pinfunction "2_2") (pintype "passive"))
    )
    (net (code "29") (name "Net-(CAN1_1C-Pad1)") (class "Default")
      (node (ref "CAN1_1C") (pin "1") (pinfunction "1_1") (pintype "passive"))
      (node (ref "CAN1_1D") (pin "1") (pinfunction "1_1") (pintype "passive"))
      (node (ref "CAN1_2C") (pin "2") (pinfunction "2_2") (pintype "passive"))
      (node (ref "CAN1_2D") (pin "2") (pinfunction "2_2") (pintype "passive"))
      (node (ref "RAN1_QC") (pin "2") (pinfunction "2_2") (pintype "passive"))
      (node (ref "RAN1_QD") (pin "2") (pinfunction "2_2") (pintype "passive"))
    )
    (net (code "30") (name "Net-(CAN2_1A-Pad1)") (class "Default")
      (node (ref "CAN2_1A") (pin "1") (pinfunction "1_1") (pintype "passive"))
      (node (ref "CAN2_1B") (pin "1") (pinfunction "1_1") (pintype "passive"))
      (node (ref "CAN2_2A") (pin "1") (pinfunction "1_1") (pintype "passive"))
      (node (ref "CAN2_2B") (pin "1") (pinfunction "1_1") (pintype "passive"))
      (node (ref "RAN2_QA") (pin "2") (pinfunction "2_2") (pintype "passive"))
      (node (ref "RAN2_QB") (pin "2") (pinfunction "2_2") (pintype "passive"))
    )
    (net (code "31") (name "Net-(CAN2_1C-Pad1)") (class "Default")
      (node (ref "CAN2_1C") (pin "1") (pinfunction "1_1") (pintype "passive"))
      (node (ref "CAN2_1D") (pin "1") (pinfunction "1_1") (pintype "passive"))
      (node (ref "CAN2_2C") (pin "2") (pinfunction "2_2") (pintype "passive"))
      (node (ref "CAN2_2D") (pin "2") (pinfunction "2_2") (pintype "passive"))
      (node (ref "RAN2_QC") (pin "2") (pinfunction "2_2") (pintype "passive"))
      (node (ref "RAN2_QD") (pin "2") (pinfunction "2_2") (pintype "passive"))
    )
    (net (code "32") (name "Net-(CAN3_1A-Pad1)") (class "Default")
      (node (ref "CAN3_1A") (pin "1") (pinfunction "1_1") (pintype "passive"))
      (node (ref "CAN3_1B") (pin "1") (pinfunction "1_1") (pintype "passive"))
      (node (ref "CAN3_2A") (pin "1") (pinfunction "1_1") (pintype "passive"))
      (node (ref "CAN3_2B") (pin "1") (pinfunction "1_1") (pintype "passive"))
      (node (ref "RAN3_QA") (pin "2") (pinfunction "2_2") (pintype "passive"))
      (node (ref "RAN3_QB") (pin "2") (pinfunction "2_2") (pintype "passive"))
    )
    (net (code "33") (name "Net-(CAN3_1C-Pad1)") (class "Default")
      (node (ref "CAN3_1C") (pin "1") (pinfunction "1_1") (pintype "passive"))
      (node (ref "CAN3_1D") (pin "1") (pinfunction "1_1") (pintype "passive"))
      (node (ref "CAN3_2C") (pin "2") (pinfunction "2_2") (pintype "passive"))
      (node (ref "CAN3_2D") (pin "2") (pinfunction "2_2") (pintype "passive"))
      (node (ref "RAN3_QC") (pin "2") (pinfunction "2_2") (pintype "passive"))
      (node (ref "RAN3_QD") (pin "2") (pinfunction "2_2") (pintype "passive"))
    )
    (net (code "34") (name "Net-(CAN4_1A-Pad1)") (class "Default")
      (node (ref "CAN4_1A") (pin "1") (pinfunction "1_1") (pintype "passive"))
      (node (ref "CAN4_1B") (pin "1") (pinfunction "1_1") (pintype "passive"))
      (node (ref "CAN4_2A") (pin "1") (pinfunction "1_1") (pintype "passive"))
      (node (ref "CAN4_2B") (pin "1") (pinfunction "1_1") (pintype "passive"))
      (node (ref "RAN4_QA") (pin "2") (pinfunction "2_2") (pintype "passive"))
      (node (ref "RAN4_QB") (pin "2") (pinfunction "2_2") (pintype "passive"))
    )
    (net (code "35") (name "Net-(CAN4_1C-Pad1)") (class "Default")
      (node (ref "CAN4_1C") (pin "1") (pinfunction "1_1") (pintype "passive"))
      (node (ref "CAN4_1D") (pin "1") (pinfunction "1_1") (pintype "passive"))
      (node (ref "CAN4_2C") (pin "2") (pinfunction "2_2") (pintype "passive"))
      (node (ref "CAN4_2D") (pin "2") (pinfunction "2_2") (pintype "passive"))
      (node (ref "RAN4_QC") (pin "2") (pinfunction "2_2") (pintype "passive"))
      (node (ref "RAN4_QD") (pin "2") (pinfunction "2_2") (pintype "passive"))
    )
    (net (code "36") (name "Net-(CAN5_1A-Pad1)") (class "Default")
      (node (ref "CAN5_1A") (pin "1") (pinfunction "1_1") (pintype "passive"))
      (node (ref "CAN5_1B") (pin "1") (pinfunction "1_1") (pintype "passive"))
      (node (ref "CAN5_2A") (pin "1") (pinfunction "1_1") (pintype "passive"))
      (node (ref "CAN5_2B") (pin "1") (pinfunction "1_1") (pintype "passive"))
      (node (ref "RAN5_QA") (pin "2") (pinfunction "2_2") (pintype "passive"))
      (node (ref "RAN5_QB") (pin "2") (pinfunction "2_2") (pintype "passive"))
    )
    (net (code "37") (name "Net-(CAN5_1C-Pad1)") (class "Default")
      (node (ref "CAN5_1C") (pin "1") (pinfunction "1_1") (pintype "passive"))
      (node (ref "CAN5_1D") (pin "1") (pinfunction "1_1") (pintype "passive"))
      (node (ref "CAN5_2C") (pin "2") (pinfunction "2_2") (pintype "passive"))
      (node (ref "CAN5_2D") (pin "2") (pinfunction "2_2") (pintype "passive"))
      (node (ref "RAN5_QC") (pin "2") (pinfunction "2_2") (pintype "passive"))
      (node (ref "RAN5_QD") (pin "2") (pinfunction "2_2") (pintype "passive"))
    )
    (net (code "38") (name "Net-(CAN6_1A-Pad1)") (class "Default")
      (node (ref "CAN6_1A") (pin "1") (pinfunction "1_1") (pintype "passive"))
      (node (ref "CAN6_1B") (pin "1") (pinfunction "1_1") (pintype "passive"))
      (node (ref "CAN6_2A") (pin "1") (pinfunction "1_1") (pintype "passive"))
      (node (ref "CAN6_2B") (pin "1") (pinfunction "1_1") (pintype "passive"))
      (node (ref "RAN6_QA") (pin "2") (pinfunction "2_2") (pintype "passive"))
      (node (ref "RAN6_QB") (pin "2") (pinfunction "2_2") (pintype "passive"))
    )
    (net (code "39") (name "Net-(CAN6_1C-Pad1)") (class "Default")
      (node (ref "CAN6_1C") (pin "1") (pinfunction "1_1") (pintype "passive"))
      (node (ref "CAN6_1D") (pin "1") (pinfunction "1_1") (pintype "passive"))
      (node (ref "CAN6_2C") (pin "2") (pinfunction "2_2") (pintype "passive"))
      (node (ref "CAN6_2D") (pin "2") (pinfunction "2_2") (pintype "passive"))
      (node (ref "RAN6_QC") (pin "2") (pinfunction "2_2") (pintype "passive"))
      (node (ref "RAN6_QD") (pin "2") (pinfunction "2_2") (pintype "passive"))
    )
    (net (code "40") (name "Net-(CM1A-Pad1)") (class "Default")
      (node (ref "CM1A") (pin "1") (pinfunction "1_1") (pintype "passive"))
      (node (ref "CM1B") (pin "1") (pinfunction "1_1") (pintype "passive"))
      (node (ref "CM2A") (pin "1") (pinfunction "1_1") (pintype "passive"))
      (node (ref "CM2B") (pin "1") (pinfunction "1_1") (pintype "passive"))
      (node (ref "RMQA") (pin "2") (pinfunction "2_2") (pintype "passive"))
      (node (ref "RMQB") (pin "2") (pinfunction "2_2") (pintype "passive"))
    )
    (net (code "41") (name "Net-(CM1C-Pad1)") (class "Default")
      (node (ref "CM1C") (pin "1") (pinfunction "1_1") (pintype "passive"))
      (node (ref "CM1D") (pin "1") (pinfunction "1_1") (pintype "passive"))
      (node (ref "CM2C") (pin "2") (pinfunction "2_2") (pintype "passive"))
      (node (ref "CM2D") (pin "2") (pinfunction "2_2") (pintype "passive"))
      (node (ref "RMQC") (pin "2") (pinfunction "2_2") (pintype "passive"))
      (node (ref "RMQD") (pin "2") (pinfunction "2_2") (pintype "passive"))
    )
    (net (code "42") (name "Net-(RAN1_QA-Pad1)") (class "Default")
      (node (ref "RAN1_QA") (pin "1") (pinfunction "1_1") (pintype "passive"))
      (node (ref "RAN1_QB") (pin "1") (pinfunction "1_1") (pintype "passive"))
      (node (ref "RAN1_QC") (pin "1") (pinfunction "1_1") (pintype "passive"))
      (node (ref "RAN1_QD") (pin "1") (pinfunction "1_1") (pintype "passive"))
      (node (ref "TPAN1_1") (pin "TP") (pinfunction "TP_TP") (pintype "input"))
      (node (ref "TPAN1_2") (pin "TP") (pinfunction "TP_TP") (pintype "input"))
    )
    (net (code "43") (name "Net-(RAN2_QA-Pad1)") (class "Default")
      (node (ref "RAN2_QA") (pin "1") (pinfunction "1_1") (pintype "passive"))
      (node (ref "RAN2_QB") (pin "1") (pinfunction "1_1") (pintype "passive"))
      (node (ref "RAN2_QC") (pin "1") (pinfunction "1_1") (pintype "passive"))
      (node (ref "RAN2_QD") (pin "1") (pinfunction "1_1") (pintype "passive"))
      (node (ref "TPAN2_1") (pin "TP") (pinfunction "TP_TP") (pintype "input"))
      (node (ref "TPAN2_2") (pin "TP") (pinfunction "TP_TP") (pintype "input"))
    )
    (net (code "44") (name "Net-(RAN3_QA-Pad1)") (class "Default")
      (node (ref "RAN3_QA") (pin "1") (pinfunction "1_1") (pintype "passive"))
      (node (ref "RAN3_QB") (pin "1") (pinfunction "1_1") (pintype "passive"))
      (node (ref "RAN3_QC") (pin "1") (pinfunction "1_1") (pintype "passive"))
      (node (ref "RAN3_QD") (pin "1") (pinfunction "1_1") (pintype "passive"))
      (node (ref "TPAN3_1") (pin "TP") (pinfunction "TP_TP") (pintype "input"))
      (node (ref "TPAN3_2") (pin "TP") (pinfunction "TP_TP") (pintype "input"))
    )
    (net (code "45") (name "Net-(RAN4_QA-Pad1)") (class "Default")
      (node (ref "RAN4_QA") (pin "1") (pinfunction "1_1") (pintype "passive"))
      (node (ref "RAN4_QB") (pin "1") (pinfunction "1_1") (pintype "passive"))
      (node (ref "RAN4_QC") (pin "1") (pinfunction "1_1") (pintype "passive"))
      (node (ref "RAN4_QD") (pin "1") (pinfunction "1_1") (pintype "passive"))
      (node (ref "TPAN4_1") (pin "TP") (pinfunction "TP_TP") (pintype "input"))
      (node (ref "TPAN4_2") (pin "TP") (pinfunction "TP_TP") (pintype "input"))
    )
    (net (code "46") (name "Net-(RAN5_QA-Pad1)") (class "Default")
      (node (ref "RAN5_QA") (pin "1") (pinfunction "1_1") (pintype "passive"))
      (node (ref "RAN5_QB") (pin "1") (pinfunction "1_1") (pintype "passive"))
      (node (ref "RAN5_QC") (pin "1") (pinfunction "1_1") (pintype "passive"))
      (node (ref "RAN5_QD") (pin "1") (pinfunction "1_1") (pintype "passive"))
      (node (ref "TPAN5_1") (pin "TP") (pinfunction "TP_TP") (pintype "input"))
      (node (ref "TPAN5_2") (pin "TP") (pinfunction "TP_TP") (pintype "input"))
    )
    (net (code "47") (name "Net-(RAN6_QA-Pad1)") (class "Default")
      (node (ref "RAN6_QA") (pin "1") (pinfunction "1_1") (pintype "passive"))
      (node (ref "RAN6_QB") (pin "1") (pinfunction "1_1") (pintype "passive"))
      (node (ref "RAN6_QC") (pin "1") (pinfunction "1_1") (pintype "passive"))
      (node (ref "RAN6_QD") (pin "1") (pinfunction "1_1") (pintype "passive"))
      (node (ref "TPAN6_1") (pin "TP") (pinfunction "TP_TP") (pintype "input"))
      (node (ref "TPAN6_2") (pin "TP") (pinfunction "TP_TP") (pintype "input"))
    )
    (net (code "48") (name "Net-(U1-AVDD)") (class "Default")
      (node (ref "CV1") (pin "1") (pinfunction "1_1") (pintype "passive"))
      (node (ref "U1") (pin "9") (pinfunction "AVDD_9") (pintype "power_in"))
    )
    (net (code "49") (name "Net-(U1-DVDD)") (class "Default")
      (node (ref "CV2") (pin "1") (pinfunction "1_1") (pintype "passive"))
      (node (ref "U1") (pin "7") (pinfunction "DVDD_7") (pintype "power_in"))
    )
    (net (code "50") (name "RST") (class "Default")
      (node (ref "SV3") (pin "2") (pinfunction "2_2") (pintype "passive"))
      (node (ref "U1") (pin "21") (pinfunction "PDOWN_21") (pintype "input"))
    )
    (net (code "51") (name "RXN") (class "Default")
      (node (ref "C1A") (pin "1") (pinfunction "1_1") (pintype "passive"))
      (node (ref "RV1") (pin "2") (pinfunction "2_2") (pintype "passive"))
      (node (ref "U1") (pin "13") (pinfunction "RXN_13") (pintype "input"))
    )
    (net (code "52") (name "RXP") (class "Default")
      (node (ref "C1B") (pin "1") (pinfunction "1_1") (pintype "passive"))
      (node (ref "RV2") (pin "1") (pinfunction "1_1") (pintype "passive"))
      (node (ref "U1") (pin "12") (pinfunction "RXP_12") (pintype "input"))
    )
    (net (code "53") (name "S1") (class "Default")
      (node (ref "SV3") (pin "12") (pinfunction "12_12") (pintype "passive"))
      (node (ref "U3") (pin "11") (pinfunction "S1_11") (pintype "input"))
      (node (ref "U4") (pin "11") (pinfunction "S1_11") (pintype "input"))
    )
    (net (code "54") (name "S2") (class "Default")
      (node (ref "SV3") (pin "11") (pinfunction "11_11") (pintype "passive"))
      (node (ref "U3") (pin "10") (pinfunction "S2_10") (pintype "input"))
      (node (ref "U4") (pin "10") (pinfunction "S2_10") (pintype "input"))
    )
    (net (code "55") (name "S3") (class "Default")
      (node (ref "SV3") (pin "10") (pinfunction "10_10") (pintype "passive"))
      (node (ref "U3") (pin "9") (pinfunction "S3_9") (pintype "input"))
      (node (ref "U4") (pin "9") (pinfunction "S3_9") (pintype "input"))
    )
    (net (code "56") (name "SCK") (class "Default")
      (node (ref "SV3") (pin "7") (pinfunction "7_7") (pintype "passive"))
      (node (ref "U1") (pin "29") (pinfunction "IF1_29") (pintype "bidirectional"))
    )
    (net (code "57") (name "TX1") (class "Default")
      (node (ref "L0A") (pin "2") (pinfunction "2_2") (pintype "passive"))
      (node (ref "U1") (pin "17") (pinfunction "TX1_17") (pintype "output"))
    )
    (net (code "58") (name "TX2") (class "Default")
      (node (ref "L0B") (pin "2") (pinfunction "2_2") (pintype "passive"))
      (node (ref "U1") (pin "15") (pinfunction "TX2_15") (pintype "output"))
    )
    (net (code "59") (name "VMID") (class "Default")
      (node (ref "CV0") (pin "1") (pinfunction "1_1") (pintype "passive"))
      (node (ref "RV1") (pin "1") (pinfunction "1_1") (pintype "passive"))
      (node (ref "RV2") (pin "2") (pinfunction "2_2") (pintype "passive"))
      (node (ref "U1") (pin "14") (pinfunction "VMID_14") (pintype "power_in"))
    )
    (net (code "60") (name "XTAL1") (class "Default")
      (node (ref "CX1") (pin "1") (pinfunction "1_1") (pintype "passive"))
      (node (ref "U1") (pin "19") (pinfunction "XTAL1_19") (pintype "input"))
      (node (ref "U2") (pin "P$1") (pinfunction "P1_P$1") (pintype "bidirectional"))
    )
    (net (code "61") (name "XTAL2") (class "Default")
      (node (ref "CX2") (pin "1") (pinfunction "1_1") (pintype "passive"))
      (node (ref "U1") (pin "20") (pinfunction "XTAL2_20") (pintype "output"))
      (node (ref "U2") (pin "P$3") (pinfunction "P3_P$3") (pintype "bidirectional"))
    )
    (net (code "62") (name "unconnected-(U1-CLKOUT{slash}OUT6-Pad22)") (class "Default")
      (node (ref "U1") (pin "22") (pinfunction "CLKOUT/OUT6_22") (pintype "output"))
    )
    (net (code "63") (name "unconnected-(U1-SIGOUT-Pad6)") (class "Default")
      (node (ref "U1") (pin "6") (pinfunction "SIGOUT_6") (pintype "output"))
    )
    (net (code "64") (name "unconnected-(U1-TDO{slash}OUT0-Pad1)") (class "Default")
      (node (ref "U1") (pin "1") (pinfunction "TDO/OUT0_1") (pintype "output"))
    )
    (net (code "65") (name "unconnected-(U3-NC-Pad7)") (class "Default")
      (node (ref "U3") (pin "7") (pinfunction "NC_7") (pintype "no_connect"))
    )
    (net (code "66") (name "unconnected-(U4-NC-Pad7)") (class "Default")
      (node (ref "U4") (pin "7") (pinfunction "NC_7") (pintype "no_connect"))
    )
  )
)
